# GSM.net
KiCad netlist of a schematic drawn in Altium Designer
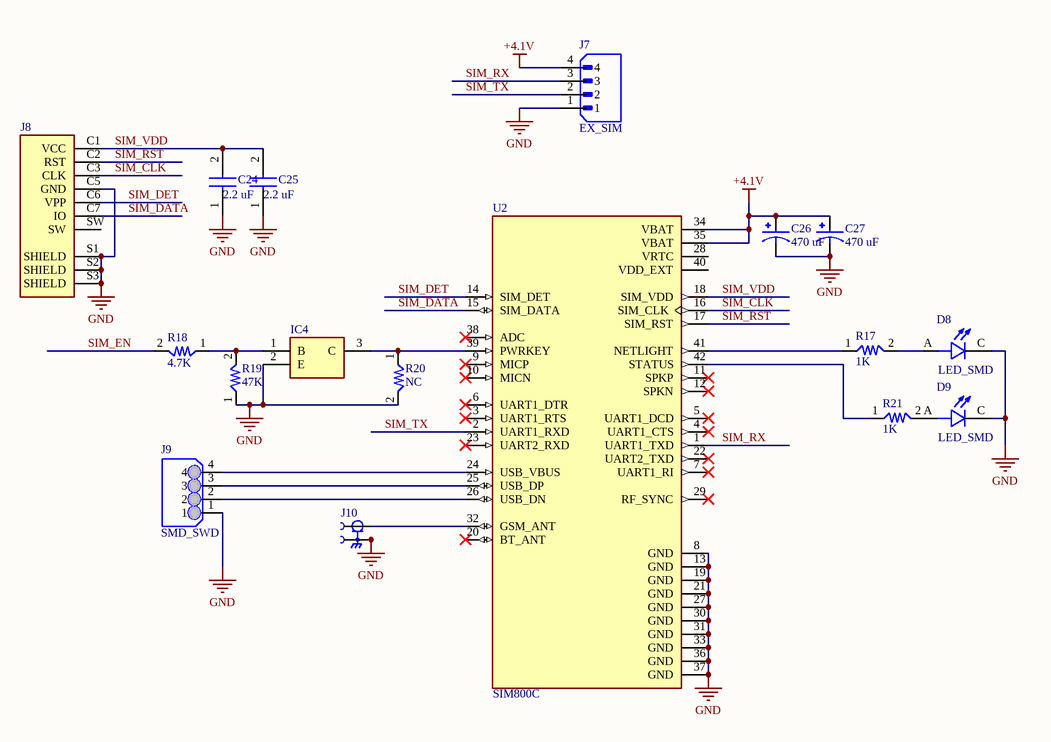
[diagram p0: GSM.SchDoc]

(export (version "E")
  (design (tool "Eeschema 10.0.6"))
  (components
    (comp (ref "C24")
      (value "2.2 uF")
      (footprint "CAP0603")
      (description "Capacitor")
      (fields
        (field (name "MANUFACTURER_PART_NUMBER") "CC0603KRX7R9BB104")
        (field (name "MOUSER PART NUMBER") "603-CC603KRX7R9BB104")
      )
      (libsource (lib "Valve_Controller_Lib") (part "CC0603KRX7R9BB104"))
    )
    (comp (ref "C25")
      (value "2.2 uF")
      (footprint "CAP0603")
      (description "Capacitor")
      (fields
        (field (name "MANUFACTURER_PART_NUMBER") "CC0603KRX7R9BB104")
        (field (name "MOUSER PART NUMBER") "603-CC603KRX7R9BB104")
      )
      (libsource (lib "Valve_Controller_Lib") (part "CC0603KRX7R9BB104"))
    )
    (comp (ref "C26")
      (value "470 uF")
      (footprint "CAPPRD350W60D800H1150")
      (description "220F 25V Aluminum Electrolytic Capacitors Radial, Can 2000 Hrs @ 105C")
      (fields (field (name "MF") "Panasonic") (field (name "MP") "EEUFC1E221"))
      (libsource (lib "EEUFC1E221") (part "EEUFC1E221"))
    )
    (comp (ref "C27")
      (value "470 uF")
      (footprint "CAPPRD350W60D800H1150")
      (description "220F 25V Aluminum Electrolytic Capacitors Radial, Can 2000 Hrs @ 105C")
      (fields (field (name "MF") "Panasonic") (field (name "MP") "EEUFC1E221"))
      (libsource (lib "EEUFC1E221") (part "EEUFC1E221"))
    )
    (comp (ref "D8")
      (value "LED_SMD")
      (footprint "LEDSC125X200X90-2N")
      (description "Red 633nm LED Indication - Discrete 2.1V 0805 (2012 Metric)")
      (fields (field (name "MF") "Dialight") (field (name "MP") "599-0110-007F"))
      (libsource (lib "Valve_Controller_Lib") (part "5990110007F"))
    )
    (comp (ref "D9")
      (value "LED_SMD")
      (footprint "LEDSC125X200X90-2N")
      (description "Red 633nm LED Indication - Discrete 2.1V 0805 (2012 Metric)")
      (fields (field (name "MF") "Dialight") (field (name "MP") "599-0110-007F"))
      (libsource (lib "Valve_Controller_Lib") (part "5990110007F"))
    )
    (comp (ref "IC4")
      (value "MMBT2222ALT1G")
      (footprint "SamacSys:SOT96P237X111-3N")
      (description "Integrated Circuit")
      (libsource (lib "*") (part "MMBT2222ALT1G"))
    )
    (comp (ref "J7")
      (value "EX_SIM")
      (footprint "JST_B4B-XH-A(LF)(SN)")
      (description "Connector Header Through Hole 4 position 0.098 (2.50mm)")
      (fields (field (name "MF") "JST Sales") (field (name "MP") "B4B-XH-A(LF)(SN)"))
      (libsource (lib "Valve_Controller_Lib") (part "B4B-XH-A(LF)(SN)"))
    )
    (comp (ref "J8")
      (value "SIM8060-6-1-14-00-A")
      (footprint "GCT_SIM8060-6-1-14-00-A")
      (description "6 Position Card Connector NANO SIM Surface Mount, Right Angle Gold")
      (fields (field (name "MF") "Global Connector Technology"))
      (libsource (lib "Valve_Controller_Lib") (part "SIM8060-6-1-14-00-A"))
    )
    (comp (ref "J9")
      (value "SMD_SWD")
      (footprint "SMD_SWD")
      (description "Connector Header Through Hole 4 position 0.098 (2.50mm)")
      (fields (field (name "MF") "JST Sales") (field (name "MP") "B4B-XH-A(LF)(SN)"))
      (libsource (lib "Valve_Controller_Lib") (part "SMD_SWD"))
    )
    (comp (ref "J10")
      (value "CONUFL001-SMD")
      (footprint "LINX_CONUFL001-SMD")
      (fields (field (name "MF") "Linx"))
      (libsource (lib "Valve_Controller_Lib") (part "CONUFL001-SMD"))
    )
    (comp (ref "R17")
      (value "1K")
      (footprint "RES0603")
      (description "Resistor")
      (fields (field (name "MANUFACTURER_PART_NUMBER") "0603WAF1001T5E"))
      (libsource (lib "Valve_Controller_Lib") (part "RES"))
    )
    (comp (ref "R18")
      (value "4.7K")
      (footprint "RES0603")
      (description "Resistor")
      (fields (field (name "MANUFACTURER_PART_NUMBER") "0603WAF1001T5E"))
      (libsource (lib "Valve_Controller_Lib") (part "RES"))
    )
    (comp (ref "R19")
      (value "47K")
      (footprint "RES0603")
      (description "Resistor")
      (fields (field (name "MANUFACTURER_PART_NUMBER") "0603WAF1001T5E"))
      (libsource (lib "Valve_Controller_Lib") (part "RES"))
    )
    (comp (ref "R20")
      (value "NC")
      (footprint "RES0603")
      (description "Resistor")
      (fields (field (name "MANUFACTURER_PART_NUMBER") "0603WAF1001T5E"))
      (libsource (lib "Valve_Controller_Lib") (part "RES"))
    )
    (comp (ref "R21")
      (value "1K")
      (footprint "RES0603")
      (description "Resistor")
      (fields (field (name "MANUFACTURER_PART_NUMBER") "0603WAF1001T5E"))
      (libsource (lib "Valve_Controller_Lib") (part "RES"))
    )
    (comp (ref "U2")
      (value "SIM800C")
      (footprint "LCC110P1570X1760X250-42N")
      (description "Module: GSM/Bluetooth; GPRS; 2G; 1800MHz, 900MHz; 85.6kbps; SMD")
      (fields (field (name "MF") "Simcom"))
      (libsource (lib "Valve_Controller_Lib") (part "SIM800C"))
    )
  )
  (nets
    (net (code "1") (name "+4.1V") (class "Default")
      (node (ref "C26") (pin "P") (pinfunction "P_P") (pintype "passive"))
      (node (ref "C27") (pin "P") (pinfunction "P_P") (pintype "passive"))
      (node (ref "J7") (pin "4") (pinfunction "4_4") (pintype "passive"))
      (node (ref "U2") (pin "34") (pinfunction "VBAT_34") (pintype "power_in"))
      (node (ref "U2") (pin "35") (pinfunction "VBAT_35") (pintype "power_in"))
    )
    (net (code "2") (name "/SIM_CLK") (class "Default")
      (node (ref "J8") (pin "C3") (pinfunction "CLK_C3") (pintype "passive"))
      (node (ref "U2") (pin "16") (pinfunction "SIM_CLK_16") (pintype "output"))
    )
    (net (code "3") (name "/SIM_DATA") (class "Default")
      (node (ref "J8") (pin "C7") (pinfunction "IO_C7") (pintype "passive"))
      (node (ref "U2") (pin "15") (pinfunction "SIM_DATA_15") (pintype "bidirectional"))
    )
    (net (code "4") (name "/SIM_DET") (class "Default")
      (node (ref "J8") (pin "C6") (pinfunction "VPP_C6") (pintype "passive"))
      (node (ref "U2") (pin "14") (pinfunction "SIM_DET_14") (pintype "input"))
    )
    (net (code "5") (name "/SIM_EN") (class "Default")
      (node (ref "R18") (pin "2") (pinfunction "2_2") (pintype "passive"))
    )
    (net (code "6") (name "/SIM_RST") (class "Default")
      (node (ref "J8") (pin "C2") (pinfunction "RST_C2") (pintype "passive"))
      (node (ref "U2") (pin "17") (pinfunction "SIM_RST_17") (pintype "output"))
    )
    (net (code "7") (name "/SIM_RX") (class "Default")
      (node (ref "J7") (pin "3") (pinfunction "3_3") (pintype "passive"))
      (node (ref "U2") (pin "1") (pinfunction "UART1_TXD_1") (pintype "output"))
    )
    (net (code "8") (name "/SIM_TX") (class "Default")
      (node (ref "J7") (pin "2") (pinfunction "2_2") (pintype "passive"))
      (node (ref "U2") (pin "2") (pinfunction "UART1_RXD_2") (pintype "input"))
    )
    (net (code "9") (name "/SIM_VDD") (class "Default")
      (node (ref "C24") (pin "2") (pinfunction "2_2") (pintype "passive"))
      (node (ref "C25") (pin "2") (pinfunction "2_2") (pintype "passive"))
      (node (ref "J8") (pin "C1") (pinfunction "VCC_C1") (pintype "passive"))
      (node (ref "U2") (pin "18") (pinfunction "SIM_VDD_18") (pintype "output"))
    )
    (net (code "10") (name "GND") (class "Default")
      (node (ref "C24") (pin "1") (pinfunction "1_1") (pintype "passive"))
      (node (ref "C25") (pin "1") (pinfunction "1_1") (pintype "passive"))
      (node (ref "C26") (pin "N") (pinfunction "N_N") (pintype "passive"))
      (node (ref "C27") (pin "N") (pinfunction "N_N") (pintype "passive"))
      (node (ref "D8") (pin "C") (pinfunction "C_C") (pintype "passive"))
      (node (ref "D9") (pin "C") (pinfunction "C_C") (pintype "passive"))
      (node (ref "IC4") (pin "2") (pinfunction "E_2") (pintype "passive"))
      (node (ref "J10") (pin "2") (pinfunction "2_2") (pintype "passive"))
      (node (ref "J10") (pin "3") (pinfunction "2_3") (pintype "passive"))
      (node (ref "J7") (pin "1") (pinfunction "1_1") (pintype "passive"))
      (node (ref "J8") (pin "C5") (pinfunction "GND_C5") (pintype "passive"))
      (node (ref "J8") (pin "S1") (pinfunction "SHIELD_S1") (pintype "passive"))
      (node (ref "J8") (pin "S2") (pinfunction "SHIELD_S2") (pintype "passive"))
      (node (ref "J8") (pin "S3") (pinfunction "SHIELD_S3") (pintype "passive"))
      (node (ref "J9") (pin "1") (pinfunction "1_1") (pintype "passive"))
      (node (ref "R19") (pin "1") (pinfunction "1_1") (pintype "passive"))
      (node (ref "R20") (pin "2") (pinfunction "2_2") (pintype "passive"))
      (node (ref "U2") (pin "13") (pinfunction "GND_13") (pintype "power_in"))
      (node (ref "U2") (pin "19") (pinfunction "GND_19") (pintype "power_in"))
      (node (ref "U2") (pin "21") (pinfunction "GND_21") (pintype "power_in"))
      (node (ref "U2") (pin "27") (pinfunction "GND_27") (pintype "power_in"))
      (node (ref "U2") (pin "30") (pinfunction "GND_30") (pintype "power_in"))
      (node (ref "U2") (pin "31") (pinfunction "GND_31") (pintype "power_in"))
      (node (ref "U2") (pin "33") (pinfunction "GND_33") (pintype "power_in"))
      (node (ref "U2") (pin "36") (pinfunction "GND_36") (pintype "power_in"))
      (node (ref "U2") (pin "37") (pinfunction "GND_37") (pintype "power_in"))
      (node (ref "U2") (pin "8") (pinfunction "GND_8") (pintype "power_in"))
    )
    (net (code "11") (name "Net-(D8-PadA)") (class "Default")
      (node (ref "D8") (pin "A") (pinfunction "A_A") (pintype "passive"))
      (node (ref "R17") (pin "2") (pinfunction "2_2") (pintype "passive"))
    )
    (net (code "12") (name "Net-(D9-PadA)") (class "Default")
      (node (ref "D9") (pin "A") (pinfunction "A_A") (pintype "passive"))
      (node (ref "R21") (pin "2") (pinfunction "2_2") (pintype "passive"))
    )
    (net (code "13") (name "Net-(IC4-B)") (class "Default")
      (node (ref "IC4") (pin "1") (pinfunction "B_1") (pintype "passive"))
      (node (ref "R18") (pin "1") (pinfunction "1_1") (pintype "passive"))
      (node (ref "R19") (pin "2") (pinfunction "2_2") (pintype "passive"))
    )
    (net (code "14") (name "Net-(IC4-C)") (class "Default")
      (node (ref "IC4") (pin "3") (pinfunction "C_3") (pintype "passive"))
      (node (ref "R20") (pin "1") (pinfunction "1_1") (pintype "passive"))
      (node (ref "U2") (pin "39") (pinfunction "PWRKEY_39") (pintype "input"))
    )
    (net (code "15") (name "Net-(U2-GSM_ANT)") (class "Default")
      (node (ref "J10") (pin "1") (pinfunction "1_1") (pintype "passive"))
      (node (ref "U2") (pin "32") (pinfunction "GSM_ANT_32") (pintype "bidirectional"))
    )
    (net (code "16") (name "Net-(U2-NETLIGHT)") (class "Default")
      (node (ref "R17") (pin "1") (pinfunction "1_1") (pintype "passive"))
      (node (ref "U2") (pin "41") (pinfunction "NETLIGHT_41") (pintype "output"))
    )
    (net (code "17") (name "Net-(U2-STATUS)") (class "Default")
      (node (ref "R21") (pin "1") (pinfunction "1_1") (pintype "passive"))
      (node (ref "U2") (pin "42") (pinfunction "STATUS_42") (pintype "output"))
    )
    (net (code "18") (name "Net-(U2-USB_DN)") (class "Default")
      (node (ref "J9") (pin "2") (pinfunction "2_2") (pintype "passive"))
      (node (ref "U2") (pin "26") (pinfunction "USB_DN_26") (pintype "bidirectional"))
    )
    (net (code "19") (name "Net-(U2-USB_DP)") (class "Default")
      (node (ref "J9") (pin "3") (pinfunction "3_3") (pintype "passive"))
      (node (ref "U2") (pin "25") (pinfunction "USB_DP_25") (pintype "bidirectional"))
    )
    (net (code "20") (name "Net-(U2-USB_VBUS)") (class "Default")
      (node (ref "J9") (pin "4") (pinfunction "4_4") (pintype "passive"))
      (node (ref "U2") (pin "24") (pinfunction "USB_VBUS_24") (pintype "input"))
    )
    (net (code "21") (name "unconnected-(J8-PadSW)") (class "Default")
      (node (ref "J8") (pin "SW") (pinfunction "SW_SW") (pintype "passive"))
    )
    (net (code "22") (name "unconnected-(U2-ADC-Pad38)") (class "Default")
      (node (ref "U2") (pin "38") (pinfunction "ADC_38") (pintype "input+no_connect"))
    )
    (net (code "23") (name "unconnected-(U2-BT_ANT-Pad20)") (class "Default")
      (node (ref "U2") (pin "20") (pinfunction "BT_ANT_20") (pintype "bidirectional+no_connect"))
    )
    (net (code "24") (name "unconnected-(U2-MICN-Pad10)") (class "Default")
      (node (ref "U2") (pin "10") (pinfunction "MICN_10") (pintype "input+no_connect"))
    )
    (net (code "25") (name "unconnected-(U2-MICP-Pad9)") (class "Default")
      (node (ref "U2") (pin "9") (pinfunction "MICP_9") (pintype "input+no_connect"))
    )
    (net (code "26") (name "unconnected-(U2-RF_SYNC-Pad29)") (class "Default")
      (node (ref "U2") (pin "29") (pinfunction "RF_SYNC_29") (pintype "output+no_connect"))
    )
    (net (code "27") (name "unconnected-(U2-SPKN-Pad12)") (class "Default")
      (node (ref "U2") (pin "12") (pinfunction "SPKN_12") (pintype "output+no_connect"))
    )
    (net (code "28") (name "unconnected-(U2-SPKP-Pad11)") (class "Default")
      (node (ref "U2") (pin "11") (pinfunction "SPKP_11") (pintype "output+no_connect"))
    )
    (net (code "29") (name "unconnected-(U2-UART1_CTS-Pad4)") (class "Default")
      (node (ref "U2") (pin "4") (pinfunction "UART1_CTS_4") (pintype "output+no_connect"))
    )
    (net (code "30") (name "unconnected-(U2-UART1_DCD-Pad5)") (class "Default")
      (node (ref "U2") (pin "5") (pinfunction "UART1_DCD_5") (pintype "output+no_connect"))
    )
    (net (code "31") (name "unconnected-(U2-UART1_DTR-Pad6)") (class "Default")
      (node (ref "U2") (pin "6") (pinfunction "UART1_DTR_6") (pintype "input+no_connect"))
    )
    (net (code "32") (name "unconnected-(U2-UART1_RI-Pad7)") (class "Default")
      (node (ref "U2") (pin "7") (pinfunction "UART1_RI_7") (pintype "output+no_connect"))
    )
    (net (code "33") (name "unconnected-(U2-UART1_RTS-Pad3)") (class "Default")
      (node (ref "U2") (pin "3") (pinfunction "UART1_RTS_3") (pintype "input+no_connect"))
    )
    (net (code "34") (name "unconnected-(U2-UART2_RXD-Pad23)") (class "Default")
      (node (ref "U2") (pin "23") (pinfunction "UART2_RXD_23") (pintype "input+no_connect"))
    )
    (net (code "35") (name "unconnected-(U2-UART2_TXD-Pad22)") (class "Default")
      (node (ref "U2") (pin "22") (pinfunction "UART2_TXD_22") (pintype "output+no_connect"))
    )
    (net (code "36") (name "unconnected-(U2-VDD_EXT-Pad40)") (class "Default")
      (node (ref "U2") (pin "40") (pinfunction "VDD_EXT_40") (pintype "power_in"))
    )
    (net (code "37") (name "unconnected-(U2-VRTC-Pad28)") (class "Default")
      (node (ref "U2") (pin "28") (pinfunction "VRTC_28") (pintype "power_in"))
    )
  )
)
